# Safety_Loop.net
KiCad netlist of a schematic drawn in Altium Designer
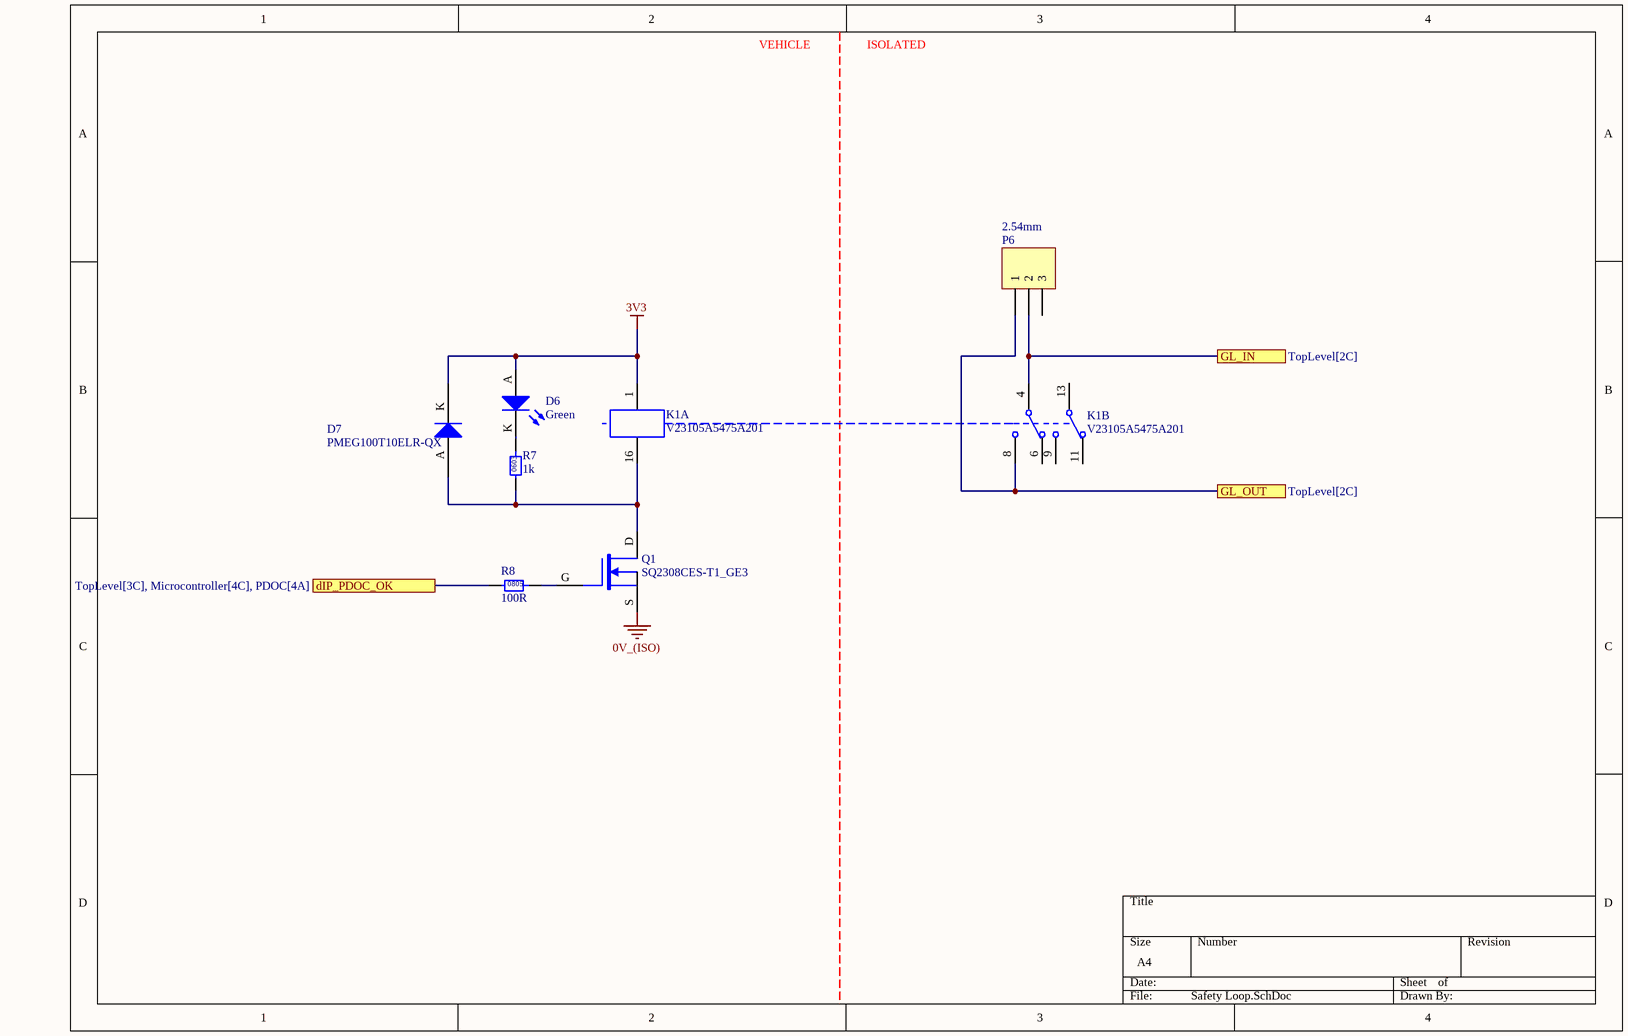
[diagram p0: Safety Loop.SchDoc]

(export (version "E")
  (design (tool "Eeschema 10.0.6"))
  (components
    (comp (ref "D6")
      (value "Green")
      (footprint "0805 LED")
      (description "Green LED Indication - Discrete 1.75V 0805 (2012 Metric)")
      (fields (field (name "PART NUMBER") "SML-210FTT86") (field (name "MANUFACTURER") "ROHM Semiconductor"))
      (libsource (lib "ts_standard_library") (part "LED"))
    )
    (comp (ref "D7")
      (value "PMEG100T10ELR-QX")
      (footprint "SODFL350X110-2N")
      (description "Diode 100 V 1A Surface Mount SOD-123W")
      (libsource (lib "Team Swinburne") (part "PMEG100T10ELR-QX"))
    )
    (comp (ref "K1")
      (value "V23105A5475A201")
      (footprint "TI 2-DIL")
      (description "5V DPDT Relay 3A 220VDC")
      (libsource (lib "Team Swinburne") (part "Symbol"))
    )
    (comp (ref "P6")
      (value "2.54mm")
      (footprint "TH 2.54mm Header 1x3")
      (fields (field (name "PART NUMBER") "TH 2.54mm Header 1x3") (field (name "CONTACT") "NA"))
      (libsource (lib "ts_standard_connectors") (part "Header 1x3"))
    )
    (comp (ref "Q1")
      (value "SQ2308CES-T1_GE3")
      (footprint "VSHY SOT-23-3")
      (description "MOSFET N-CH 60V 2.3A SOT23")
      (fields
        (field (name "MANUFACTURER") "Vishay Siliconix")
        (field (name "DIGIKEY PART NUMBER") "SQ2308CES-T1_GE3CT-ND")
        (field (name "PUBLISHER") "Altium Limited")
      )
      (libsource (lib "ts_standard_library") (part "MOSFET-N"))
    )
    (comp (ref "R7")
      (value "1k")
      (footprint "0603")
      (fields
        (field (name "PART NUMBER") "RC0603FR-071KL")
        (field (name "MANUFACTURER") "YAGEO")
        (field (name "TOLERANCE") "0.01")
      )
      (libsource (lib "ts_standard_library") (part "Resistor 0603"))
    )
    (comp (ref "R8")
      (value "100R")
      (footprint "0805")
      (fields
        (field (name "PART NUMBER") "RC0805FR07100RL")
        (field (name "MANUFACTURER") "YAGEO")
        (field (name "TOLERANCE") "0.01")
      )
      (libsource (lib "ts_standard_library") (part "Resistor 0805"))
    )
  )
  (nets
    (net (code "1") (name "/GL_IN") (class "Default")
      (node (ref "K1") (pin "4") (pinfunction "4_4") (pintype "passive"))
      (node (ref "P6") (pin "2") (pinfunction "2_2") (pintype "passive"))
    )
    (net (code "2") (name "/GL_OUT") (class "Default")
      (node (ref "K1") (pin "8") (pinfunction "8_8") (pintype "passive"))
      (node (ref "P6") (pin "1") (pinfunction "1_1") (pintype "passive"))
    )
    (net (code "3") (name "/dIP_PDOC_OK") (class "Default")
      (node (ref "R8") (pin "1") (pinfunction "1_1") (pintype "passive"))
    )
    (net (code "4") (name "0V_(ISO)") (class "Default")
      (node (ref "Q1") (pin "S") (pinfunction "S_S") (pintype "passive"))
    )
    (net (code "5") (name "3V3") (class "Default")
      (node (ref "D6") (pin "A") (pinfunction "A_A") (pintype "passive"))
      (node (ref "D7") (pin "K") (pintype "passive"))
      (node (ref "K1") (pin "1") (pinfunction "1_1") (pintype "passive"))
    )
    (net (code "6") (name "Net-(D6-PadK)") (class "Default")
      (node (ref "D6") (pin "K") (pinfunction "K_K") (pintype "passive"))
      (node (ref "R7") (pin "2") (pinfunction "2_2") (pintype "passive"))
    )
    (net (code "7") (name "Net-(D7-PadA)") (class "Default")
      (node (ref "D7") (pin "A") (pintype "passive"))
      (node (ref "K1") (pin "16") (pinfunction "16_16") (pintype "passive"))
      (node (ref "Q1") (pin "D") (pinfunction "D_D") (pintype "passive"))
      (node (ref "R7") (pin "1") (pinfunction "1_1") (pintype "passive"))
    )
    (net (code "8") (name "Net-(Q1-PadG)") (class "Default")
      (node (ref "Q1") (pin "G") (pinfunction "G_G") (pintype "passive"))
      (node (ref "R8") (pin "2") (pinfunction "2_2") (pintype "passive"))
    )
    (net (code "9") (name "unconnected-(K1-Pad6)") (class "Default")
      (node (ref "K1") (pin "6") (pinfunction "6_6") (pintype "passive"))
    )
    (net (code "10") (name "unconnected-(K1-Pad9)") (class "Default")
      (node (ref "K1") (pin "9") (pinfunction "9_9") (pintype "passive"))
    )
    (net (code "11") (name "unconnected-(K1-Pad11)") (class "Default")
      (node (ref "K1") (pin "11") (pinfunction "11_11") (pintype "passive"))
    )
    (net (code "12") (name "unconnected-(K1-Pad13)") (class "Default")
      (node (ref "K1") (pin "13") (pinfunction "13_13") (pintype "passive"))
    )
    (net (code "13") (name "unconnected-(P6-Pad3)") (class "Default")
      (node (ref "P6") (pin "3") (pinfunction "3_3") (pintype "passive"))
    )
  )
)
